# acionadorIncendio.net
KiCad netlist of a schematic drawn in Altium Designer
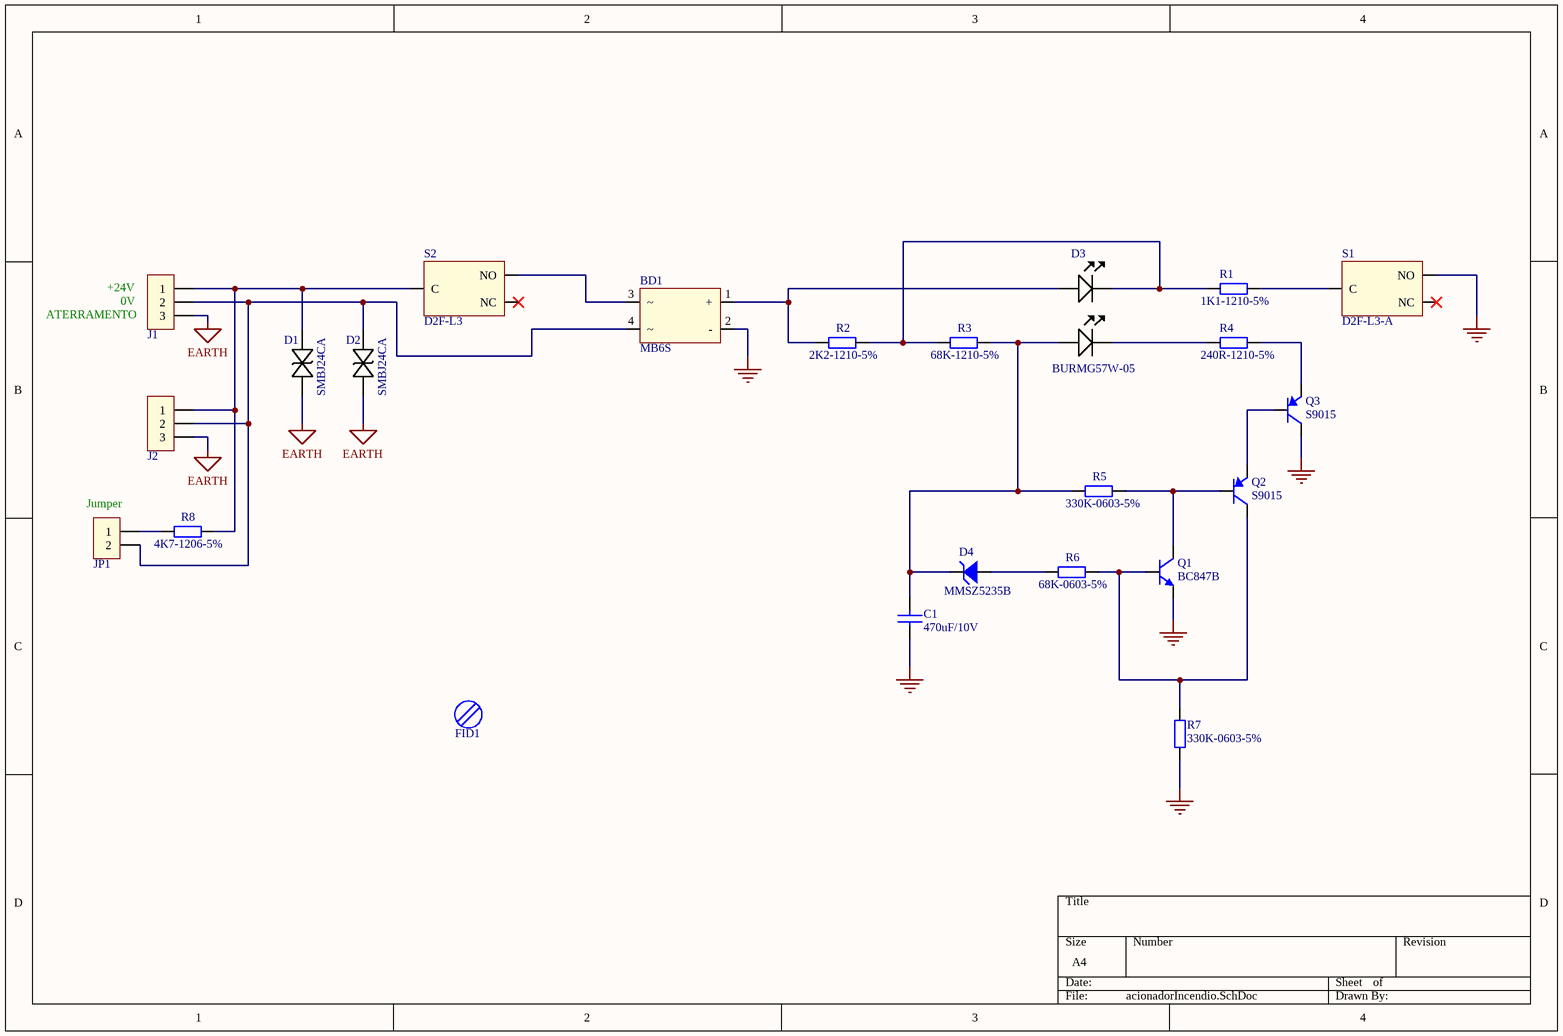
[diagram p0: acionadorIncendio.SchDoc]

(export (version "E")
  (design (tool "Eeschema 10.0.6"))
  (components
    (comp (ref "BD1")
      (value "MB6S")
      (footprint "DIO-BG-SMD_4P-L4.7-W4.0-P2.50-LS7.0-TL")
      (description "PONTE RETIFICADORA MB6S")
      (libsource (lib "biblioteca_acionador") (part "MB6S"))
    )
    (comp (ref "C1")
      (value "470uF/10V")
      (footprint "CAP-SMD_BD10.0-L10.3-W10.3-LS11.3-FD")
      (description "CAPACITOR ELETROLITICO 470UF 10V SMD")
      (libsource (lib "biblioteca_acionador") (part "CAP470UF"))
    )
    (comp (ref "D1")
      (value "SMBJ24CA")
      (footprint "SMBJ50CA")
      (libsource (lib "biblioteca_acionador") (part "SMBJ24CA"))
    )
    (comp (ref "D2")
      (value "SMBJ24CA")
      (footprint "SMBJ50CA")
      (libsource (lib "biblioteca_acionador") (part "SMBJ24CA"))
    )
    (comp (ref "D3")
      (value "BURMG57W-05")
      (footprint "BURMG57W")
      (description "LED BURMG57W-05")
      (libsource (lib "biblioteca_acionador") (part "BURMG57W-05"))
    )
    (comp (ref "D4")
      (value "MMSZ5235B")
      (footprint "SOD-123-2")
      (description "DIODO ZENER MMSZ5235B")
      (libsource (lib "biblioteca_acionador") (part "MMSZ5235B"))
    )
    (comp (ref "FID1")
      (value "MEC_FIDUCIAL_1")
      (footprint "Fiducial_1")
      (libsource (lib "LIB_ROSSI") (part "FIDUCIAL"))
    )
    (comp (ref "J1")
      (value "BORNE")
      (footprint "BORNE3")
      (description "BORNE 3 VIAS")
      (libsource (lib "biblioteca_acionador") (part "BORNE3"))
    )
    (comp (ref "J2")
      (value "BORNE")
      (footprint "BORNE3")
      (description "BORNE 3 VIAS")
      (libsource (lib "biblioteca_acionador") (part "BORNE3"))
    )
    (comp (ref "JP1")
      (value "JUMPER")
      (footprint "HEADER1X2")
      (description "BARRA PINOS 2 PINOS 180 P-2.5MM / CAPA MINI JUMPER MKBL 020B")
      (libsource (lib "biblioteca_acionador") (part "HEADER_1X2"))
    )
    (comp (ref "Q1")
      (value "BC847B")
      (footprint "SOT-23")
      (description "TRANSISTOR BC847B SOT-23-3 SMD")
      (libsource (lib "biblioteca_acionador") (part "BC847B"))
    )
    (comp (ref "Q2")
      (value "S9015")
      (footprint "SOT-23")
      (description "TRANSISTOR PNP S9015 SOT23-3 SMD")
      (libsource (lib "biblioteca_acionador") (part "S9015"))
    )
    (comp (ref "Q3")
      (value "S9015")
      (footprint "SOT-23")
      (description "TRANSISTOR PNP S9015 SOT23-3 SMD")
      (libsource (lib "biblioteca_acionador") (part "S9015"))
    )
    (comp (ref "R1")
      (value "1K1-1210-5%")
      (footprint "1210-RES")
      (description "RESISTOR 1K1 1210 5%")
      (libsource (lib "biblioteca_acionador") (part "RES1K1_1210"))
    )
    (comp (ref "R2")
      (value "2K2-1210-5%")
      (footprint "1210-RES")
      (description "RESISTOR 2K2 1210 5%")
      (libsource (lib "biblioteca_acionador") (part "RES2K2_1210"))
    )
    (comp (ref "R3")
      (value "68K-1210-5%")
      (footprint "1210-RES")
      (description "RESISTOR 68K 1210 5%")
      (libsource (lib "biblioteca_acionador") (part "RES68K_1210"))
    )
    (comp (ref "R4")
      (value "240R-1210-5%")
      (footprint "1210-RES")
      (description "RESISTOR 240R 1210 5%")
      (libsource (lib "biblioteca_acionador") (part "RES240R_1210"))
    )
    (comp (ref "R5")
      (value "330K-0603-5%")
      (footprint "0603-RES")
      (description "RESISTOR 330K 0603 5%")
      (libsource (lib "biblioteca_acionador") (part "RES330K_0603"))
    )
    (comp (ref "R6")
      (value "68K-0603-5%")
      (footprint "0603-RES")
      (description "RESISTOR 68K 0603 5%")
      (libsource (lib "biblioteca_acionador") (part "RES68K_0603"))
    )
    (comp (ref "R7")
      (value "330K-0603-5%")
      (footprint "0603-RES")
      (description "RESISTOR 330K 0603 5%")
      (libsource (lib "biblioteca_acionador") (part "RES330K_0603"))
    )
    (comp (ref "R8")
      (value "4K7-1206-5%")
      (footprint "1206-RES")
      (description "RESISTOR 4K7 1206 5%")
      (libsource (lib "biblioteca_acionador") (part "RES4K7_1206"))
    )
    (comp (ref "S1")
      (value "D2F-L3-A")
      (footprint "D2F-L3-A")
      (description "CHAVE INTERRUPTOR D2F-L3-A")
      (libsource (lib "biblioteca_acionador") (part "D2F-L3-A"))
    )
    (comp (ref "S2")
      (value "D2F-L3")
      (footprint "D2F-L3")
      (description "CHAVE INTERRUPTOR D2F-L3")
      (libsource (lib "biblioteca_acionador") (part "D2F-L3"))
    )
  )
  (nets
    (net (code "1") (name "EARTH") (class "Default")
      (node (ref "D1") (pin "2") (pinfunction "2_2") (pintype "passive"))
      (node (ref "D2") (pin "2") (pinfunction "2_2") (pintype "passive"))
      (node (ref "J1") (pin "3") (pinfunction "3_3") (pintype "passive"))
      (node (ref "J2") (pin "3") (pinfunction "3_3") (pintype "passive"))
    )
    (net (code "2") (name "GND") (class "Default")
      (node (ref "BD1") (pin "2") (pinfunction "-_2") (pintype "passive"))
      (node (ref "C1") (pin "2") (pinfunction "2_2") (pintype "passive"))
      (node (ref "Q1") (pin "2") (pinfunction "E_2") (pintype "passive"))
      (node (ref "Q3") (pin "2") (pinfunction "E_2") (pintype "passive"))
      (node (ref "R7") (pin "1") (pinfunction "1_1") (pintype "passive"))
      (node (ref "S1") (pin "2") (pinfunction "NO_2") (pintype "passive"))
    )
    (net (code "3") (name "Net-(BD1-+)") (class "Default")
      (node (ref "BD1") (pin "1") (pinfunction "+_1") (pintype "passive"))
      (node (ref "D3") (pin "1") (pinfunction "1_1") (pintype "passive"))
      (node (ref "R2") (pin "1") (pinfunction "1_1") (pintype "passive"))
    )
    (net (code "4") (name "Net-(BD1-~-Pad4)") (class "Default")
      (node (ref "BD1") (pin "4") (pinfunction "~_4") (pintype "passive"))
      (node (ref "D2") (pin "1") (pinfunction "1_1") (pintype "passive"))
      (node (ref "J1") (pin "2") (pinfunction "2_2") (pintype "passive"))
      (node (ref "J2") (pin "2") (pinfunction "2_2") (pintype "passive"))
      (node (ref "JP1") (pin "2") (pinfunction "2_2") (pintype "passive"))
    )
    (net (code "5") (name "Net-(D3-Pad2)") (class "Default")
      (node (ref "D3") (pin "2") (pinfunction "2_2") (pintype "passive"))
      (node (ref "R1") (pin "1") (pinfunction "1_1") (pintype "passive"))
      (node (ref "R2") (pin "2") (pinfunction "2_2") (pintype "passive"))
      (node (ref "R3") (pin "1") (pinfunction "1_1") (pintype "passive"))
    )
    (net (code "6") (name "Net-(D3-Pad4)") (class "Default")
      (node (ref "D3") (pin "4") (pinfunction "4_4") (pintype "passive"))
      (node (ref "R4") (pin "1") (pinfunction "1_1") (pintype "passive"))
    )
    (net (code "7") (name "Net-(D4-A)") (class "Default")
      (node (ref "D4") (pin "2") (pinfunction "A_2") (pintype "passive"))
      (node (ref "R6") (pin "1") (pinfunction "1_1") (pintype "passive"))
    )
    (net (code "8") (name "Net-(D4-K)") (class "Default")
      (node (ref "C1") (pin "1") (pinfunction "1_1") (pintype "passive"))
      (node (ref "D3") (pin "3") (pinfunction "3_3") (pintype "passive"))
      (node (ref "D4") (pin "1") (pinfunction "K_1") (pintype "passive"))
      (node (ref "R3") (pin "2") (pinfunction "2_2") (pintype "passive"))
      (node (ref "R5") (pin "1") (pinfunction "1_1") (pintype "passive"))
    )
    (net (code "9") (name "Net-(JP1-Pad1)") (class "Default")
      (node (ref "JP1") (pin "1") (pinfunction "1_1") (pintype "passive"))
      (node (ref "R8") (pin "1") (pinfunction "1_1") (pintype "passive"))
    )
    (net (code "10") (name "Net-(Q1-10)") (class "Default")
      (node (ref "Q1") (pin "1") (pinfunction "10_1") (pintype "passive"))
      (node (ref "Q2") (pin "2") (pinfunction "E_2") (pintype "passive"))
      (node (ref "R6") (pin "2") (pinfunction "2_2") (pintype "passive"))
      (node (ref "R7") (pin "2") (pinfunction "2_2") (pintype "passive"))
    )
    (net (code "11") (name "Net-(Q1-C)") (class "Default")
      (node (ref "Q1") (pin "3") (pinfunction "C_3") (pintype "passive"))
      (node (ref "Q2") (pin "1") (pinfunction "10_1") (pintype "passive"))
      (node (ref "R5") (pin "2") (pinfunction "2_2") (pintype "passive"))
    )
    (net (code "12") (name "Net-(Q2-C)") (class "Default")
      (node (ref "Q2") (pin "3") (pinfunction "C_3") (pintype "passive"))
      (node (ref "Q3") (pin "1") (pinfunction "10_1") (pintype "passive"))
    )
    (net (code "13") (name "Net-(Q3-C)") (class "Default")
      (node (ref "Q3") (pin "3") (pinfunction "C_3") (pintype "passive"))
      (node (ref "R4") (pin "2") (pinfunction "2_2") (pintype "passive"))
    )
    (net (code "14") (name "Net-(S1-C)") (class "Default")
      (node (ref "R1") (pin "2") (pinfunction "2_2") (pintype "passive"))
      (node (ref "S1") (pin "1") (pinfunction "C_1") (pintype "passive"))
    )
    (net (code "15") (name "Net-(S2-C)") (class "Default")
      (node (ref "D1") (pin "1") (pinfunction "1_1") (pintype "passive"))
      (node (ref "J1") (pin "1") (pinfunction "1_1") (pintype "passive"))
      (node (ref "J2") (pin "1") (pinfunction "1_1") (pintype "passive"))
      (node (ref "R8") (pin "2") (pinfunction "2_2") (pintype "passive"))
      (node (ref "S2") (pin "1") (pinfunction "C_1") (pintype "passive"))
    )
    (net (code "16") (name "Net-(S2-NO)") (class "Default")
      (node (ref "BD1") (pin "3") (pinfunction "~_3") (pintype "passive"))
      (node (ref "S2") (pin "2") (pinfunction "NO_2") (pintype "passive"))
    )
    (net (code "17") (name "unconnected-(S1-NC-Pad3)") (class "Default")
      (node (ref "S1") (pin "3") (pinfunction "NC_3") (pintype "passive+no_connect"))
    )
    (net (code "18") (name "unconnected-(S2-NC-Pad3)") (class "Default")
      (node (ref "S2") (pin "3") (pinfunction "NC_3") (pintype "passive+no_connect"))
    )
  )
)
